# AmigaUSBMouseV2.net
KiCad netlist of a schematic drawn in EAGLE
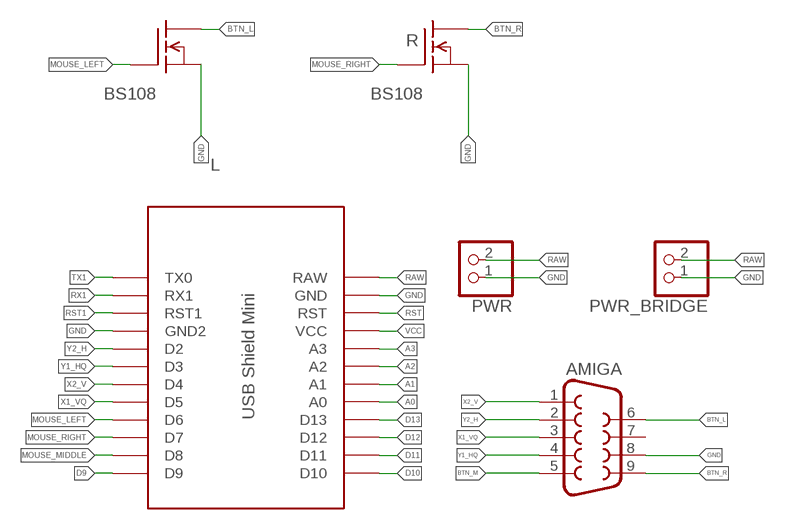
[diagram p0: schematic, sheet 1]

(export (version "E")
  (design (tool "Eeschema 10.0.6"))
  (components
    (comp (ref "AMIGA")
      (value "F09D")
      (footprint "eagle-import:F09D")
      (libsource (lib "eagle-import") (part "F09D"))
    )
    (comp (ref "L")
      (value "BS108")
      (footprint "eagle-import:TO92-INLINE")
      (libsource (lib "eagle-import") (part "FQN1N50CI"))
    )
    (comp (ref "PWR")
      (value "PINHD-1X2")
      (footprint "eagle-import:1X02")
      (libsource (lib "eagle-import") (part "PINHD-1X2"))
    )
    (comp (ref "PWR_BRIDGE")
      (value "PINHD-1X2")
      (footprint "eagle-import:1X02")
      (libsource (lib "eagle-import") (part "PINHD-1X2"))
    )
    (comp (ref "R")
      (value "BS108")
      (footprint "eagle-import:TO92-INLINE")
      (libsource (lib "eagle-import") (part "FQN1N50CI"))
    )
    (comp (ref "U$2")
      (value "USB-SHIELD-MINI")
      (footprint "eagle-import:USB-SHIELD-MINI")
      (libsource (lib "eagle-import") (part "USB-SHIELD-MINI"))
    )
  )
  (nets
    (net (code "1") (name "A0") (class "Default")
      (node (ref "U$2") (pin "A0") (pinfunction "A0_A0") (pintype "bidirectional"))
    )
    (net (code "2") (name "A1") (class "Default")
      (node (ref "U$2") (pin "A1") (pinfunction "A1_A1") (pintype "bidirectional"))
    )
    (net (code "3") (name "A2") (class "Default")
      (node (ref "U$2") (pin "A2") (pinfunction "A2_A2") (pintype "bidirectional"))
    )
    (net (code "4") (name "A3") (class "Default")
      (node (ref "U$2") (pin "A3") (pinfunction "A3_A3") (pintype "bidirectional"))
    )
    (net (code "5") (name "BTN_L") (class "Default")
      (node (ref "AMIGA") (pin "6") (pinfunction "6_6") (pintype "passive"))
      (node (ref "L") (pin "1") (pinfunction "D_1") (pintype "passive"))
    )
    (net (code "6") (name "BTN_M") (class "Default")
      (node (ref "AMIGA") (pin "5") (pinfunction "5_5") (pintype "passive"))
    )
    (net (code "7") (name "BTN_R") (class "Default")
      (node (ref "AMIGA") (pin "9") (pinfunction "9_9") (pintype "passive"))
      (node (ref "R") (pin "1") (pinfunction "D_1") (pintype "passive"))
    )
    (net (code "8") (name "D9") (class "Default")
      (node (ref "U$2") (pin "D9") (pinfunction "D9_D9") (pintype "bidirectional"))
    )
    (net (code "9") (name "D10") (class "Default")
      (node (ref "U$2") (pin "D10") (pinfunction "D10_D10") (pintype "bidirectional"))
    )
    (net (code "10") (name "D11") (class "Default")
      (node (ref "U$2") (pin "D11") (pinfunction "D11_D11") (pintype "bidirectional"))
    )
    (net (code "11") (name "D12") (class "Default")
      (node (ref "U$2") (pin "D12") (pinfunction "D12_D12") (pintype "bidirectional"))
    )
    (net (code "12") (name "D13") (class "Default")
      (node (ref "U$2") (pin "D13") (pinfunction "D13_D13") (pintype "bidirectional"))
    )
    (net (code "13") (name "GND") (class "Default")
      (node (ref "AMIGA") (pin "8") (pinfunction "8_8") (pintype "passive"))
      (node (ref "L") (pin "3") (pinfunction "S_3") (pintype "passive"))
      (node (ref "PWR") (pin "1") (pinfunction "1_1") (pintype "passive"))
      (node (ref "PWR_BRIDGE") (pin "1") (pinfunction "1_1") (pintype "passive"))
      (node (ref "R") (pin "3") (pinfunction "S_3") (pintype "passive"))
      (node (ref "U$2") (pin "GND") (pinfunction "GND_GND") (pintype "bidirectional"))
      (node (ref "U$2") (pin "GND1") (pinfunction "GND2_GND1") (pintype "bidirectional"))
    )
    (net (code "14") (name "MOUSE_LEFT") (class "Default")
      (node (ref "L") (pin "2") (pinfunction "G_2") (pintype "passive"))
      (node (ref "U$2") (pin "D6") (pinfunction "D6_D6") (pintype "bidirectional"))
    )
    (net (code "15") (name "MOUSE_MIDDLE") (class "Default")
      (node (ref "U$2") (pin "D8") (pinfunction "D8_D8") (pintype "bidirectional"))
    )
    (net (code "16") (name "MOUSE_RIGHT") (class "Default")
      (node (ref "R") (pin "2") (pinfunction "G_2") (pintype "passive"))
      (node (ref "U$2") (pin "D7") (pinfunction "D7_D7") (pintype "bidirectional"))
    )
    (net (code "17") (name "RAW") (class "Default")
      (node (ref "PWR") (pin "2") (pinfunction "2_2") (pintype "passive"))
      (node (ref "PWR_BRIDGE") (pin "2") (pinfunction "2_2") (pintype "passive"))
      (node (ref "U$2") (pin "RAW") (pinfunction "RAW_RAW") (pintype "bidirectional"))
    )
    (net (code "18") (name "RST") (class "Default")
      (node (ref "U$2") (pin "RST") (pinfunction "RST_RST") (pintype "bidirectional"))
    )
    (net (code "19") (name "RST1") (class "Default")
      (node (ref "U$2") (pin "RST1") (pinfunction "RST1_RST1") (pintype "bidirectional"))
    )
    (net (code "20") (name "RX1") (class "Default")
      (node (ref "U$2") (pin "RX1") (pinfunction "RX1_RX1") (pintype "bidirectional"))
    )
    (net (code "21") (name "TX1") (class "Default")
      (node (ref "U$2") (pin "TX0") (pinfunction "TX0_TX0") (pintype "bidirectional"))
    )
    (net (code "22") (name "VCC") (class "Default")
      (node (ref "U$2") (pin "VCC") (pinfunction "VCC_VCC") (pintype "bidirectional"))
    )
    (net (code "23") (name "X1_VQ") (class "Default")
      (node (ref "AMIGA") (pin "3") (pinfunction "3_3") (pintype "passive"))
      (node (ref "U$2") (pin "D5") (pinfunction "D5_D5") (pintype "bidirectional"))
    )
    (net (code "24") (name "X2_V") (class "Default")
      (node (ref "AMIGA") (pin "1") (pinfunction "1_1") (pintype "passive"))
      (node (ref "U$2") (pin "D4") (pinfunction "D4_D4") (pintype "bidirectional"))
    )
    (net (code "25") (name "Y1_HQ") (class "Default")
      (node (ref "AMIGA") (pin "4") (pinfunction "4_4") (pintype "passive"))
      (node (ref "U$2") (pin "D3") (pinfunction "D3_D3") (pintype "bidirectional"))
    )
    (net (code "26") (name "Y2_H") (class "Default")
      (node (ref "AMIGA") (pin "2") (pinfunction "2_2") (pintype "passive"))
      (node (ref "U$2") (pin "D2") (pinfunction "D2_D2") (pintype "bidirectional"))
    )
    (net (code "27") (name "unconnected-(AMIGA-Pad7)") (class "Default")
      (node (ref "AMIGA") (pin "7") (pinfunction "7_7") (pintype "passive"))
    )
  )
)
